# FlybackCape.net
KiCad netlist of a schematic drawn in EAGLE
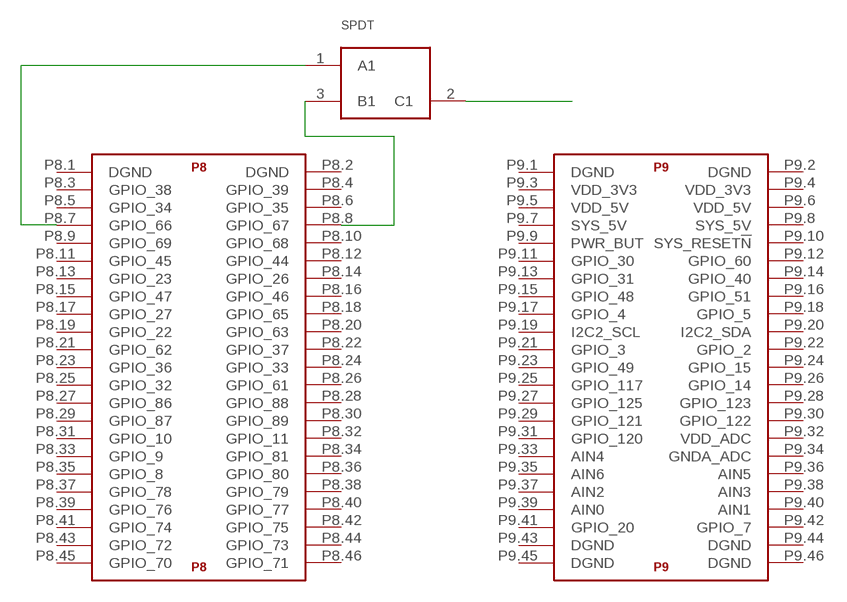
[diagram p0: schematic, sheet 1]
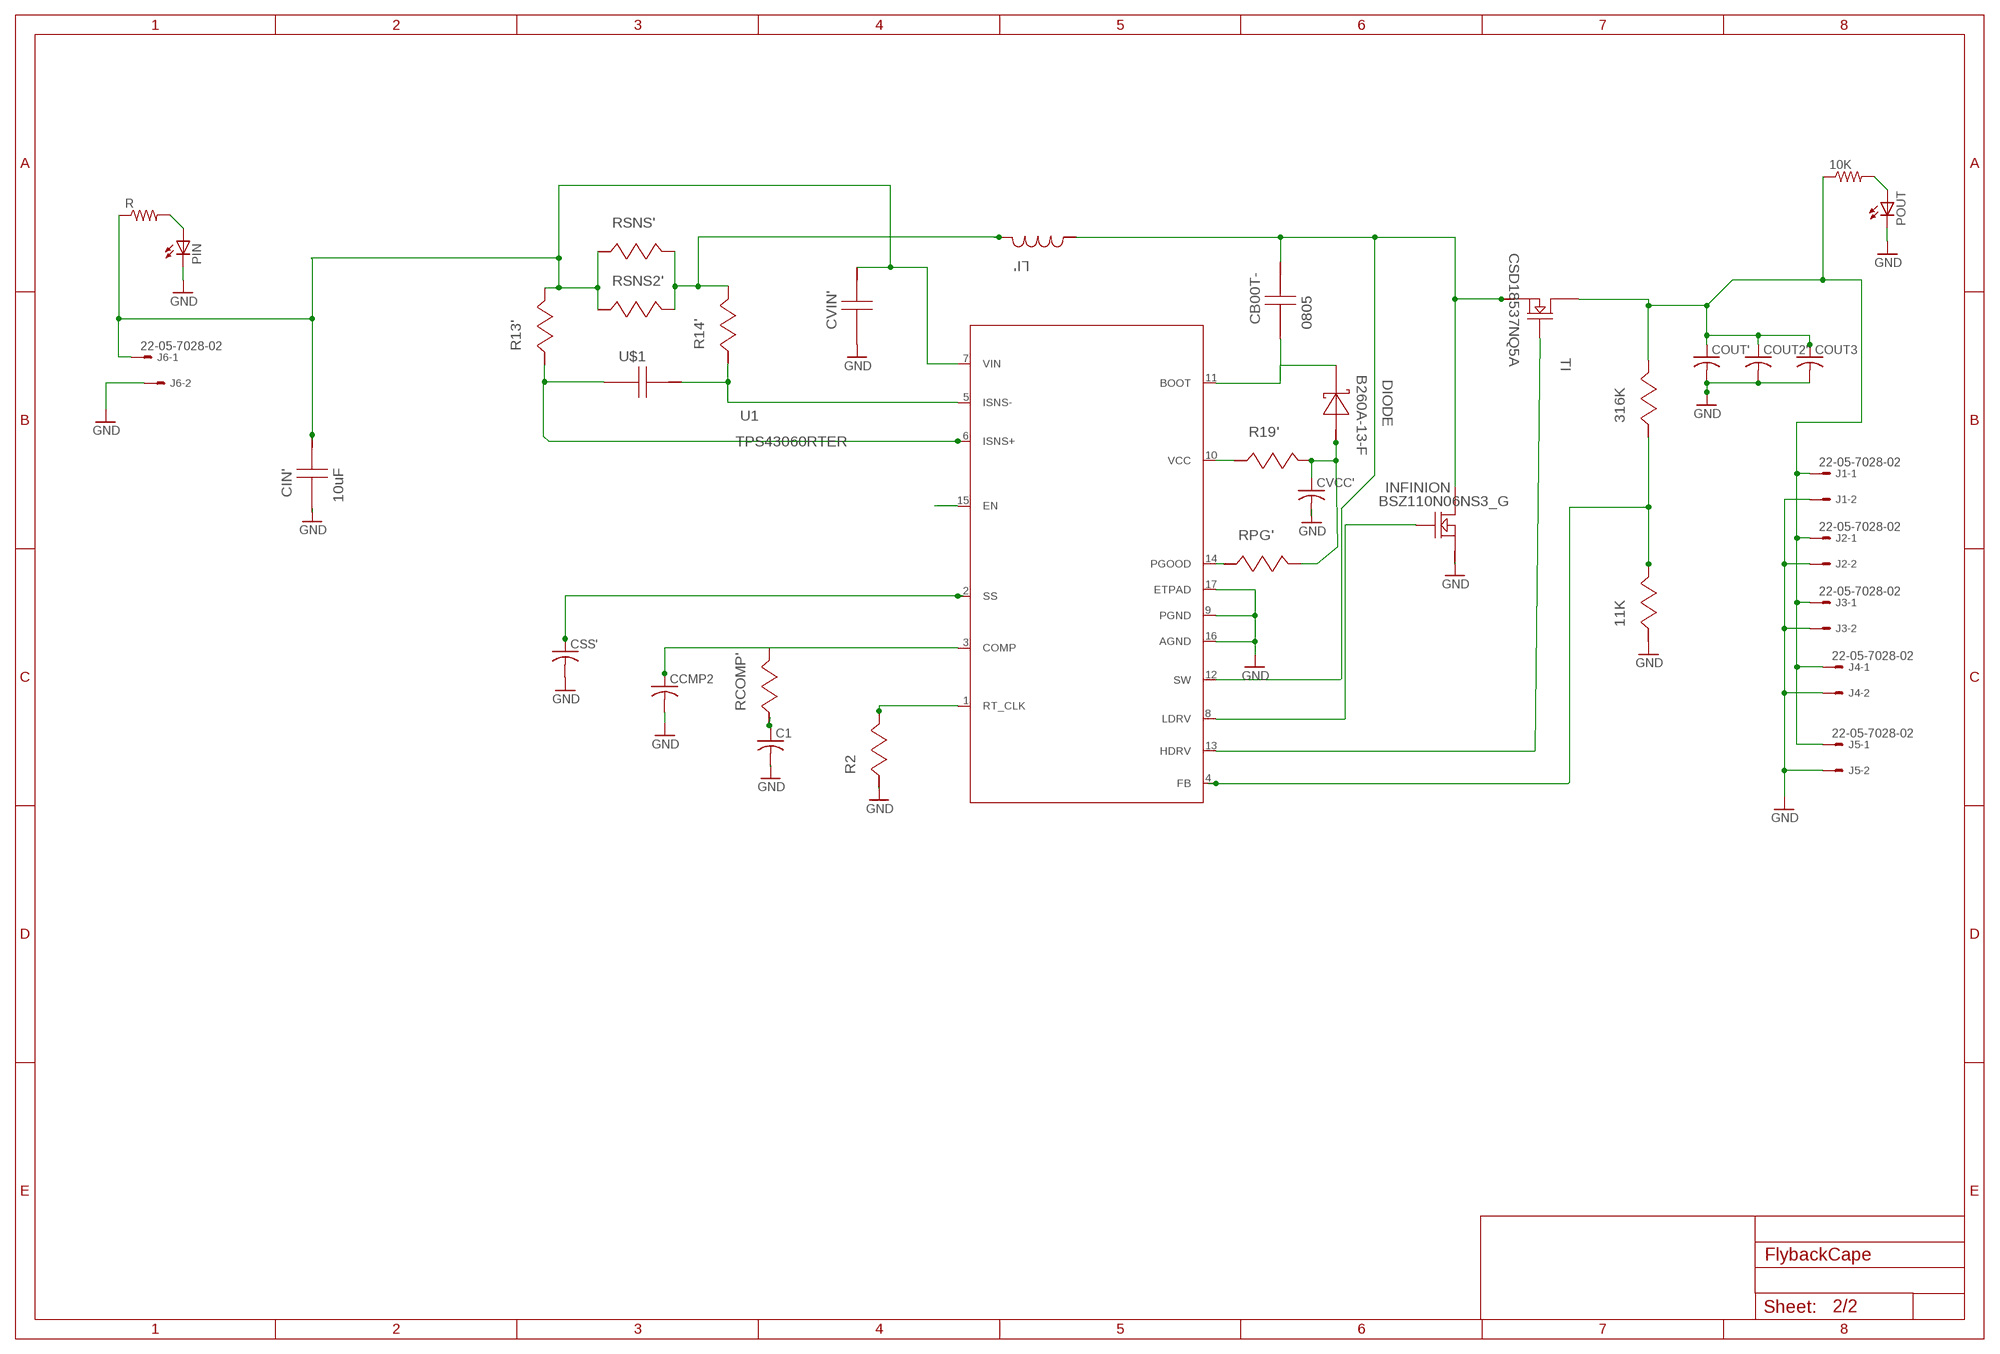
[diagram p1: schematic, sheet 2]

(export (version "E")
  (design (tool "Eeschema 10.0.6"))
  (components
    (comp (ref "10K")
      (value "R-US_R1206")
      (footprint "eagle-import:R1206")
      (libsource (lib "eagle-import") (part "R-US_R1206"))
    )
    (comp (ref "11K")
      (value "CRCW0402110KFKED")
      (footprint "eagle-import:0402")
      (fields (field (name "POWER") "0.063") (field (name "TOLERANCE") "1.0"))
      (libsource (lib "eagle-import") (part "CRCW0402110KFKED"))
    )
    (comp (ref "316K")
      (value "CRCW0402110KFKED")
      (footprint "eagle-import:0402")
      (fields (field (name "POWER") "0.063") (field (name "TOLERANCE") "1.0"))
      (libsource (lib "eagle-import") (part "CRCW0402110KFKED"))
    )
    (comp (ref "C1")
      (value "C-USC0805")
      (footprint "eagle-import:C0805")
      (libsource (lib "eagle-import") (part "C-USC0805"))
    )
    (comp (ref "CB00T-")
      (value "0805")
      (footprint "eagle-import:0805")
      (fields (field (name "MANUFACTURER_PART_NUMBER") "08053C104KAT2A"))
      (libsource (lib "eagle-import") (part "08053C104KAT2A"))
    )
    (comp (ref "CCMP2")
      (value "C-USC0402")
      (footprint "eagle-import:C0402")
      (libsource (lib "eagle-import") (part "C-USC0402"))
    )
    (comp (ref "CIN'")
      (value "10uF")
      (footprint "eagle-import:1210")
      (fields (field (name "MANUFACTURER_PART_NUMBER") "C3225X7S2A475M"))
      (libsource (lib "eagle-import") (part "C3225X7S2A475M"))
    )
    (comp (ref "COUT'")
      (value "C-USC1812")
      (footprint "eagle-import:C1812")
      (libsource (lib "eagle-import") (part "C-USC1812"))
    )
    (comp (ref "COUT2'")
      (value "C-USC1812")
      (footprint "eagle-import:C1812")
      (libsource (lib "eagle-import") (part "C-USC1812"))
    )
    (comp (ref "COUT3")
      (value "C-USC1812")
      (footprint "eagle-import:C1812")
      (libsource (lib "eagle-import") (part "C-USC1812"))
    )
    (comp (ref "CSS'")
      (value "C-USC0603K")
      (footprint "eagle-import:C0603K")
      (libsource (lib "eagle-import") (part "C-USC0603K"))
    )
    (comp (ref "CVCC'")
      (value "C-USC0805")
      (footprint "eagle-import:C0805")
      (libsource (lib "eagle-import") (part "C-USC0805"))
    )
    (comp (ref "CVIN'")
      (value "08053C104KAT2A")
      (footprint "eagle-import:0805")
      (libsource (lib "eagle-import") (part "08053C104KAT2A"))
    )
    (comp (ref "DIODE")
      (value "B260A-13-F")
      (footprint "eagle-import:SMA")
      (libsource (lib "eagle-import") (part "B260A-13-F"))
    )
    (comp (ref "INFINION")
      (value "BSZ110N06NS3_G")
      (footprint "eagle-import:PG-TSDSON-8")
      (fields (field (name "MANUFACTURER_PART_NUMBER") "BSZ110N06NS3 G"))
      (libsource (lib "eagle-import") (part "BSZ110N06NS3_G"))
    )
    (comp (ref "J1")
      (value "22-05-7028-02")
      (footprint "eagle-import:7395-02")
      (libsource (lib "eagle-import") (part "22-?-0205-7028"))
    )
    (comp (ref "J2")
      (value "22-05-7028-02")
      (footprint "eagle-import:7395-02")
      (libsource (lib "eagle-import") (part "22-?-0205-7028"))
    )
    (comp (ref "J3")
      (value "22-05-7028-02")
      (footprint "eagle-import:7395-02")
      (libsource (lib "eagle-import") (part "22-?-0205-7028"))
    )
    (comp (ref "J4")
      (value "22-05-7028-02")
      (footprint "eagle-import:7395-02")
      (libsource (lib "eagle-import") (part "22-?-0205-7028"))
    )
    (comp (ref "J5")
      (value "22-05-7028-02")
      (footprint "eagle-import:7395-02")
      (libsource (lib "eagle-import") (part "22-?-0205-7028"))
    )
    (comp (ref "J6")
      (value "22-05-7028-02")
      (footprint "eagle-import:7395-02")
      (libsource (lib "eagle-import") (part "22-?-0205-7028"))
    )
    (comp (ref "LI'")
      (value "MSS1210-153MEB")
      (footprint "eagle-import:MSS1210")
      (fields (field (name "MANUFACTURER") "CoilCraft"))
      (libsource (lib "eagle-import") (part "MSS1210-153MEB"))
    )
    (comp (ref "PIN")
      (value "LEDCHIPLED_1206")
      (footprint "eagle-import:CHIPLED_1206")
      (libsource (lib "eagle-import") (part "LEDCHIPLED_1206"))
    )
    (comp (ref "POUT")
      (value "LEDCHIPLED_1206")
      (footprint "eagle-import:CHIPLED_1206")
      (libsource (lib "eagle-import") (part "LEDCHIPLED_1206"))
    )
    (comp (ref "R")
      (value "R-US_R1206")
      (footprint "eagle-import:R1206")
      (libsource (lib "eagle-import") (part "R-US_R1206"))
    )
    (comp (ref "R2")
      (value "CRCW04023K32FKED")
      (footprint "eagle-import:0402")
      (fields (field (name "POWER") "0.063") (field (name "TOLERANCE") "1.0"))
      (libsource (lib "eagle-import") (part "CRCW04023K32FKED"))
    )
    (comp (ref "R13'")
      (value "CRCW04022R00FKED")
      (footprint "eagle-import:0402")
      (fields (field (name "POWER") "0.063") (field (name "TOLERANCE") "1.0"))
      (libsource (lib "eagle-import") (part "CRCW04022R00FKED"))
    )
    (comp (ref "R14'")
      (value "CRCW04022R00FKED")
      (footprint "eagle-import:0402")
      (fields (field (name "POWER") "0.063") (field (name "TOLERANCE") "1.0"))
      (libsource (lib "eagle-import") (part "CRCW04022R00FKED"))
    )
    (comp (ref "R19'")
      (value "CRCW04022R00FKED")
      (footprint "eagle-import:0402")
      (fields (field (name "POWER") "0.063") (field (name "TOLERANCE") "1.0"))
      (libsource (lib "eagle-import") (part "CRCW04022R00FKED"))
    )
    (comp (ref "RCOMP'")
      (value "CRCW04023K32FKED")
      (footprint "eagle-import:0402")
      (fields (field (name "POWER") "0.063") (field (name "TOLERANCE") "1.0"))
      (libsource (lib "eagle-import") (part "CRCW04023K32FKED"))
    )
    (comp (ref "RPG'")
      (value "CRCW0402100KFKED")
      (footprint "eagle-import:0402")
      (fields (field (name "POWER") "0.063") (field (name "TOLERANCE") "1.0"))
      (libsource (lib "eagle-import") (part "CRCW0402100KFKED"))
    )
    (comp (ref "RSNS'")
      (value "PRL1632-R012-F-T1")
      (footprint "eagle-import:1206")
      (fields (field (name "POWER") "1.0"))
      (libsource (lib "eagle-import") (part "PRL1632-R012-F-T1"))
    )
    (comp (ref "RSNS2'")
      (value "PRL1632-R012-F-T1")
      (footprint "eagle-import:1206")
      (fields (field (name "POWER") "1.0"))
      (libsource (lib "eagle-import") (part "PRL1632-R012-F-T1"))
    )
    (comp (ref "TI")
      (value "CSD18537NQ5A")
      (footprint "eagle-import:TRANS_NEXFET_Q5A")
      (libsource (lib "eagle-import") (part "CSD18537NQ5A"))
    )
    (comp (ref "U$1")
      (value "GRM188R61C106MA73D")
      (footprint "eagle-import:0603")
      (libsource (lib "eagle-import") (part "GRM188R61C106MA73D"))
    )
    (comp (ref "U1")
      (value "TPS43060RTER")
      (footprint "eagle-import:S-PVQFN-N16")
      (libsource (lib "eagle-import") (part "TPS43060RTER"))
    )
    (comp (ref "SPDT")
      (value "SPDT_SWITCH")
      (footprint "eagle-import:SPDT")
      (libsource (lib "eagle-import") (part "SPDT_SWITCH"))
    )
    (comp (ref "U$2")
      (value "BEAGLE_BONE_BLACK_CAPE")
      (footprint "eagle-import:BEAGLE_BONE_BLACK_CAPE")
      (libsource (lib "eagle-import") (part "BEAGLE_BONE_BLACK_CAPE"))
    )
  )
  (nets
    (net (code "1") (name "EN") (class "Default")
      (node (ref "SPDT") (pin "2") (pinfunction "C1_2") (pintype "bidirectional"))
      (node (ref "U1") (pin "15") (pinfunction "EN_15") (pintype "passive"))
    )
    (net (code "2") (name "GND") (class "Default")
      (node (ref "11K") (pin "2") (pinfunction "2_2") (pintype "passive"))
      (node (ref "C1") (pin "2") (pinfunction "2_2") (pintype "passive"))
      (node (ref "CCMP2") (pin "2") (pinfunction "2_2") (pintype "passive"))
      (node (ref "CIN'") (pin "2") (pinfunction "2_2") (pintype "passive"))
      (node (ref "COUT'") (pin "2") (pinfunction "2_2") (pintype "passive"))
      (node (ref "COUT2'") (pin "2") (pinfunction "2_2") (pintype "passive"))
      (node (ref "COUT3") (pin "2") (pinfunction "2_2") (pintype "passive"))
      (node (ref "CSS'") (pin "2") (pinfunction "2_2") (pintype "passive"))
      (node (ref "CVCC'") (pin "2") (pinfunction "2_2") (pintype "passive"))
      (node (ref "CVIN'") (pin "2") (pinfunction "2_2") (pintype "passive"))
      (node (ref "INFINION") (pin "1") (pinfunction "SOURCE_2_1") (pintype "passive"))
      (node (ref "INFINION") (pin "2") (pinfunction "SOURCE_2_2") (pintype "passive"))
      (node (ref "INFINION") (pin "3") (pinfunction "SOURCE_2_3") (pintype "passive"))
      (node (ref "J1") (pin "2") (pinfunction "S_2") (pintype "passive"))
      (node (ref "J2") (pin "2") (pinfunction "S_2") (pintype "passive"))
      (node (ref "J3") (pin "2") (pinfunction "S_2") (pintype "passive"))
      (node (ref "J4") (pin "2") (pinfunction "S_2") (pintype "passive"))
      (node (ref "J5") (pin "2") (pinfunction "S_2") (pintype "passive"))
      (node (ref "J6") (pin "2") (pinfunction "S_2") (pintype "passive"))
      (node (ref "PIN") (pin "C") (pinfunction "C_C") (pintype "passive"))
      (node (ref "POUT") (pin "C") (pinfunction "C_C") (pintype "passive"))
      (node (ref "R2") (pin "2") (pinfunction "2_2") (pintype "passive"))
      (node (ref "U1") (pin "16") (pinfunction "AGND_16") (pintype "passive"))
      (node (ref "U1") (pin "17") (pinfunction "ETPAD_17") (pintype "passive"))
      (node (ref "U1") (pin "9") (pinfunction "PGND_9") (pintype "passive"))
    )
    (net (code "3") (name "Net-(10K-Pad2)") (class "Default")
      (node (ref "10K") (pin "2") (pinfunction "2_2") (pintype "passive"))
      (node (ref "POUT") (pin "A") (pinfunction "A_A") (pintype "passive"))
    )
    (net (code "4") (name "Net-(C1-Pad1)") (class "Default")
      (node (ref "C1") (pin "1") (pinfunction "1_1") (pintype "passive"))
      (node (ref "RCOMP'") (pin "2") (pinfunction "2_2") (pintype "passive"))
    )
    (net (code "5") (name "Net-(DIODE-A)") (class "Default")
      (node (ref "CVCC'") (pin "1") (pinfunction "1_1") (pintype "passive"))
      (node (ref "DIODE") (pin "2") (pinfunction "A_2") (pintype "passive"))
      (node (ref "R19'") (pin "1") (pinfunction "1_1") (pintype "passive"))
      (node (ref "RPG'") (pin "1") (pinfunction "1_1") (pintype "passive"))
    )
    (net (code "6") (name "Net-(DIODE-K)") (class "Default")
      (node (ref "CB00T-") (pin "2") (pinfunction "2_2") (pintype "passive"))
      (node (ref "DIODE") (pin "1") (pinfunction "K_1") (pintype "passive"))
      (node (ref "U1") (pin "11") (pinfunction "BOOT_11") (pintype "passive"))
    )
    (net (code "7") (name "Net-(INFINION-GATE)") (class "Default")
      (node (ref "INFINION") (pin "4") (pinfunction "GATE_4") (pintype "passive"))
      (node (ref "U1") (pin "8") (pinfunction "LDRV_8") (pintype "passive"))
    )
    (net (code "8") (name "Net-(J1A-S)") (class "Default")
      (node (ref "10K") (pin "1") (pinfunction "1_1") (pintype "passive"))
      (node (ref "316K") (pin "1") (pinfunction "1_1") (pintype "passive"))
      (node (ref "COUT'") (pin "1") (pinfunction "1_1") (pintype "passive"))
      (node (ref "COUT2'") (pin "1") (pinfunction "1_1") (pintype "passive"))
      (node (ref "COUT3") (pin "1") (pinfunction "1_1") (pintype "passive"))
      (node (ref "J1") (pin "1") (pinfunction "S_1") (pintype "passive"))
      (node (ref "J2") (pin "1") (pinfunction "S_1") (pintype "passive"))
      (node (ref "J3") (pin "1") (pinfunction "S_1") (pintype "passive"))
      (node (ref "J4") (pin "1") (pinfunction "S_1") (pintype "passive"))
      (node (ref "J5") (pin "1") (pinfunction "S_1") (pintype "passive"))
      (node (ref "TI") (pin "5") (pinfunction "DRAIN_2_5") (pintype "passive"))
      (node (ref "TI") (pin "6") (pinfunction "DRAIN_2_6") (pintype "passive"))
      (node (ref "TI") (pin "7") (pinfunction "DRAIN_2_7") (pintype "passive"))
      (node (ref "TI") (pin "8") (pinfunction "DRAIN_2_8") (pintype "passive"))
      (node (ref "TI") (pin "9") (pinfunction "DRAIN_2_9") (pintype "passive"))
    )
    (net (code "9") (name "Net-(J6A-S)") (class "Default")
      (node (ref "CIN'") (pin "1") (pinfunction "1_1") (pintype "passive"))
      (node (ref "CVIN'") (pin "1") (pinfunction "1_1") (pintype "passive"))
      (node (ref "J6") (pin "1") (pinfunction "S_1") (pintype "passive"))
      (node (ref "R") (pin "1") (pinfunction "1_1") (pintype "passive"))
      (node (ref "R13'") (pin "1") (pinfunction "1_1") (pintype "passive"))
      (node (ref "RSNS'") (pin "2") (pinfunction "2_2") (pintype "passive"))
      (node (ref "RSNS2'") (pin "2") (pinfunction "2_2") (pintype "passive"))
      (node (ref "U1") (pin "7") (pinfunction "VIN_7") (pintype "passive"))
    )
    (net (code "10") (name "Net-(LI'-Pad1)") (class "Default")
      (node (ref "LI'") (pin "1") (pinfunction "1_1") (pintype "passive"))
      (node (ref "R14'") (pin "1") (pinfunction "1_1") (pintype "passive"))
      (node (ref "RSNS'") (pin "1") (pinfunction "1_1") (pintype "passive"))
      (node (ref "RSNS2'") (pin "1") (pinfunction "1_1") (pintype "passive"))
    )
    (net (code "11") (name "Net-(PIN-PadA)") (class "Default")
      (node (ref "PIN") (pin "A") (pinfunction "A_A") (pintype "passive"))
      (node (ref "R") (pin "2") (pinfunction "2_2") (pintype "passive"))
    )
    (net (code "12") (name "Net-(SPDT-A1)") (class "Default")
      (node (ref "SPDT") (pin "1") (pinfunction "A1_1") (pintype "bidirectional"))
      (node (ref "U$2") (pin "P8.7") (pinfunction "GPIO_66_P8.7") (pintype "bidirectional"))
    )
    (net (code "13") (name "Net-(SPDT-B1)") (class "Default")
      (node (ref "SPDT") (pin "3") (pinfunction "B1_3") (pintype "bidirectional"))
      (node (ref "U$2") (pin "P8.8") (pinfunction "GPIO_67_P8.8") (pintype "bidirectional"))
    )
    (net (code "14") (name "Net-(TI-GATE)") (class "Default")
      (node (ref "TI") (pin "4") (pinfunction "GATE_4") (pintype "passive"))
      (node (ref "U1") (pin "13") (pinfunction "HDRV_13") (pintype "passive"))
    )
    (net (code "15") (name "Net-(U1-COMP)") (class "Default")
      (node (ref "CCMP2") (pin "1") (pinfunction "1_1") (pintype "passive"))
      (node (ref "RCOMP'") (pin "1") (pinfunction "1_1") (pintype "passive"))
      (node (ref "U1") (pin "3") (pinfunction "COMP_3") (pintype "passive"))
    )
    (net (code "16") (name "Net-(U1-FB)") (class "Default")
      (node (ref "11K") (pin "1") (pinfunction "1_1") (pintype "passive"))
      (node (ref "316K") (pin "2") (pinfunction "2_2") (pintype "passive"))
      (node (ref "U1") (pin "4") (pinfunction "FB_4") (pintype "passive"))
    )
    (net (code "17") (name "Net-(U1-ISNS+)") (class "Default")
      (node (ref "R13'") (pin "2") (pinfunction "2_2") (pintype "passive"))
      (node (ref "U$1") (pin "2") (pinfunction "2_2") (pintype "passive"))
      (node (ref "U1") (pin "6") (pinfunction "ISNS+_6") (pintype "passive"))
    )
    (net (code "18") (name "Net-(U1-ISNS-)") (class "Default")
      (node (ref "R14'") (pin "2") (pinfunction "2_2") (pintype "passive"))
      (node (ref "U$1") (pin "1") (pinfunction "1_1") (pintype "passive"))
      (node (ref "U1") (pin "5") (pinfunction "ISNS-_5") (pintype "passive"))
    )
    (net (code "19") (name "Net-(U1-PGOOD)") (class "Default")
      (node (ref "RPG'") (pin "2") (pinfunction "2_2") (pintype "passive"))
      (node (ref "U1") (pin "14") (pinfunction "PGOOD_14") (pintype "passive"))
    )
    (net (code "20") (name "Net-(U1-RT_CLK)") (class "Default")
      (node (ref "R2") (pin "1") (pinfunction "1_1") (pintype "passive"))
      (node (ref "U1") (pin "1") (pinfunction "RT_CLK_1") (pintype "passive"))
    )
    (net (code "21") (name "Net-(U1-SS)") (class "Default")
      (node (ref "CSS'") (pin "1") (pinfunction "1_1") (pintype "passive"))
      (node (ref "U1") (pin "2") (pinfunction "SS_2") (pintype "passive"))
    )
    (net (code "22") (name "Net-(U1-SW)") (class "Default")
      (node (ref "CB00T-") (pin "1") (pinfunction "1_1") (pintype "passive"))
      (node (ref "INFINION") (pin "5") (pinfunction "DRAIN_2_5") (pintype "passive"))
      (node (ref "INFINION") (pin "6") (pinfunction "DRAIN_2_6") (pintype "passive"))
      (node (ref "INFINION") (pin "7") (pinfunction "DRAIN_2_7") (pintype "passive"))
      (node (ref "INFINION") (pin "8") (pinfunction "DRAIN_2_8") (pintype "passive"))
      (node (ref "INFINION") (pin "9") (pinfunction "DRAIN_2_9") (pintype "passive"))
      (node (ref "LI'") (pin "2") (pinfunction "2_2") (pintype "passive"))
      (node (ref "TI") (pin "1") (pinfunction "SOURCE_2_1") (pintype "passive"))
      (node (ref "TI") (pin "2") (pinfunction "SOURCE_2_2") (pintype "passive"))
      (node (ref "TI") (pin "3") (pinfunction "SOURCE_2_3") (pintype "passive"))
      (node (ref "U1") (pin "12") (pinfunction "SW_12") (pintype "passive"))
    )
    (net (code "23") (name "Net-(U1-VCC)") (class "Default")
      (node (ref "R19'") (pin "2") (pinfunction "2_2") (pintype "passive"))
      (node (ref "U1") (pin "10") (pinfunction "VCC_10") (pintype "passive"))
    )
    (net (code "24") (name "unconnected-(U$2A-DGND-PadP8.1)") (class "Default")
      (node (ref "U$2") (pin "P8.1") (pinfunction "DGND_P8.1") (pintype "bidirectional"))
    )
    (net (code "25") (name "unconnected-(U$2A-DGND-PadP8.2)") (class "Default")
      (node (ref "U$2") (pin "P8.2") (pinfunction "DGND_P8.2") (pintype "bidirectional"))
    )
    (net (code "26") (name "unconnected-(U$2A-GPIO_8-PadP8.35)") (class "Default")
      (node (ref "U$2") (pin "P8.35") (pinfunction "GPIO_8_P8.35") (pintype "bidirectional"))
    )
    (net (code "27") (name "unconnected-(U$2A-GPIO_9-PadP8.33)") (class "Default")
      (node (ref "U$2") (pin "P8.33") (pinfunction "GPIO_9_P8.33") (pintype "bidirectional"))
    )
    (net (code "28") (name "unconnected-(U$2A-GPIO_10-PadP8.31)") (class "Default")
      (node (ref "U$2") (pin "P8.31") (pinfunction "GPIO_10_P8.31") (pintype "bidirectional"))
    )
    (net (code "29") (name "unconnected-(U$2A-GPIO_11-PadP8.32)") (class "Default")
      (node (ref "U$2") (pin "P8.32") (pinfunction "GPIO_11_P8.32") (pintype "bidirectional"))
    )
    (net (code "30") (name "unconnected-(U$2A-GPIO_22-PadP8.19)") (class "Default")
      (node (ref "U$2") (pin "P8.19") (pinfunction "GPIO_22_P8.19") (pintype "bidirectional"))
    )
    (net (code "31") (name "unconnected-(U$2A-GPIO_23-PadP8.13)") (class "Default")
      (node (ref "U$2") (pin "P8.13") (pinfunction "GPIO_23_P8.13") (pintype "bidirectional"))
    )
    (net (code "32") (name "unconnected-(U$2A-GPIO_26-PadP8.14)") (class "Default")
      (node (ref "U$2") (pin "P8.14") (pinfunction "GPIO_26_P8.14") (pintype "bidirectional"))
    )
    (net (code "33") (name "unconnected-(U$2A-GPIO_27-PadP8.17)") (class "Default")
      (node (ref "U$2") (pin "P8.17") (pinfunction "GPIO_27_P8.17") (pintype "bidirectional"))
    )
    (net (code "34") (name "unconnected-(U$2A-GPIO_32-PadP8.25)") (class "Default")
      (node (ref "U$2") (pin "P8.25") (pinfunction "GPIO_32_P8.25") (pintype "bidirectional"))
    )
    (net (code "35") (name "unconnected-(U$2A-GPIO_33-PadP8.24)") (class "Default")
      (node (ref "U$2") (pin "P8.24") (pinfunction "GPIO_33_P8.24") (pintype "bidirectional"))
    )
    (net (code "36") (name "unconnected-(U$2A-GPIO_34-PadP8.5)") (class "Default")
      (node (ref "U$2") (pin "P8.5") (pinfunction "GPIO_34_P8.5") (pintype "bidirectional"))
    )
    (net (code "37") (name "unconnected-(U$2A-GPIO_35-PadP8.6)") (class "Default")
      (node (ref "U$2") (pin "P8.6") (pinfunction "GPIO_35_P8.6") (pintype "bidirectional"))
    )
    (net (code "38") (name "unconnected-(U$2A-GPIO_36-PadP8.23)") (class "Default")
      (node (ref "U$2") (pin "P8.23") (pinfunction "GPIO_36_P8.23") (pintype "bidirectional"))
    )
    (net (code "39") (name "unconnected-(U$2A-GPIO_37-PadP8.22)") (class "Default")
      (node (ref "U$2") (pin "P8.22") (pinfunction "GPIO_37_P8.22") (pintype "bidirectional"))
    )
    (net (code "40") (name "unconnected-(U$2A-GPIO_38-PadP8.3)") (class "Default")
      (node (ref "U$2") (pin "P8.3") (pinfunction "GPIO_38_P8.3") (pintype "bidirectional"))
    )
    (net (code "41") (name "unconnected-(U$2A-GPIO_39-PadP8.4)") (class "Default")
      (node (ref "U$2") (pin "P8.4") (pinfunction "GPIO_39_P8.4") (pintype "bidirectional"))
    )
    (net (code "42") (name "unconnected-(U$2A-GPIO_44-PadP8.12)") (class "Default")
      (node (ref "U$2") (pin "P8.12") (pinfunction "GPIO_44_P8.12") (pintype "bidirectional"))
    )
    (net (code "43") (name "unconnected-(U$2A-GPIO_45-PadP8.11)") (class "Default")
      (node (ref "U$2") (pin "P8.11") (pinfunction "GPIO_45_P8.11") (pintype "bidirectional"))
    )
    (net (code "44") (name "unconnected-(U$2A-GPIO_46-PadP8.16)") (class "Default")
      (node (ref "U$2") (pin "P8.16") (pinfunction "GPIO_46_P8.16") (pintype "bidirectional"))
    )
    (net (code "45") (name "unconnected-(U$2A-GPIO_47-PadP8.15)") (class "Default")
      (node (ref "U$2") (pin "P8.15") (pinfunction "GPIO_47_P8.15") (pintype "bidirectional"))
    )
    (net (code "46") (name "unconnected-(U$2A-GPIO_61-PadP8.26)") (class "Default")
      (node (ref "U$2") (pin "P8.26") (pinfunction "GPIO_61_P8.26") (pintype "bidirectional"))
    )
    (net (code "47") (name "unconnected-(U$2A-GPIO_62-PadP8.21)") (class "Default")
      (node (ref "U$2") (pin "P8.21") (pinfunction "GPIO_62_P8.21") (pintype "bidirectional"))
    )
    (net (code "48") (name "unconnected-(U$2A-GPIO_63-PadP8.20)") (class "Default")
      (node (ref "U$2") (pin "P8.20") (pinfunction "GPIO_63_P8.20") (pintype "bidirectional"))
    )
    (net (code "49") (name "unconnected-(U$2A-GPIO_65-PadP8.18)") (class "Default")
      (node (ref "U$2") (pin "P8.18") (pinfunction "GPIO_65_P8.18") (pintype "bidirectional"))
    )
    (net (code "50") (name "unconnected-(U$2A-GPIO_68-PadP8.10)") (class "Default")
      (node (ref "U$2") (pin "P8.10") (pinfunction "GPIO_68_P8.10") (pintype "bidirectional"))
    )
    (net (code "51") (name "unconnected-(U$2A-GPIO_69-PadP8.9)") (class "Default")
      (node (ref "U$2") (pin "P8.9") (pinfunction "GPIO_69_P8.9") (pintype "bidirectional"))
    )
    (net (code "52") (name "unconnected-(U$2A-GPIO_70-PadP8.45)") (class "Default")
      (node (ref "U$2") (pin "P8.45") (pinfunction "GPIO_70_P8.45") (pintype "bidirectional"))
    )
    (net (code "53") (name "unconnected-(U$2A-GPIO_71-PadP8.46)") (class "Default")
      (node (ref "U$2") (pin "P8.46") (pinfunction "GPIO_71_P8.46") (pintype "bidirectional"))
    )
    (net (code "54") (name "unconnected-(U$2A-GPIO_72-PadP8.43)") (class "Default")
      (node (ref "U$2") (pin "P8.43") (pinfunction "GPIO_72_P8.43") (pintype "bidirectional"))
    )
    (net (code "55") (name "unconnected-(U$2A-GPIO_73-PadP8.44)") (class "Default")
      (node (ref "U$2") (pin "P8.44") (pinfunction "GPIO_73_P8.44") (pintype "bidirectional"))
    )
    (net (code "56") (name "unconnected-(U$2A-GPIO_74-PadP8.41)") (class "Default")
      (node (ref "U$2") (pin "P8.41") (pinfunction "GPIO_74_P8.41") (pintype "bidirectional"))
    )
    (net (code "57") (name "unconnected-(U$2A-GPIO_75-PadP8.42)") (class "Default")
      (node (ref "U$2") (pin "P8.42") (pinfunction "GPIO_75_P8.42") (pintype "bidirectional"))
    )
    (net (code "58") (name "unconnected-(U$2A-GPIO_76-PadP8.39)") (class "Default")
      (node (ref "U$2") (pin "P8.39") (pinfunction "GPIO_76_P8.39") (pintype "bidirectional"))
    )
    (net (code "59") (name "unconnected-(U$2A-GPIO_77-PadP8.40)") (class "Default")
      (node (ref "U$2") (pin "P8.40") (pinfunction "GPIO_77_P8.40") (pintype "bidirectional"))
    )
    (net (code "60") (name "unconnected-(U$2A-GPIO_78-PadP8.37)") (class "Default")
      (node (ref "U$2") (pin "P8.37") (pinfunction "GPIO_78_P8.37") (pintype "bidirectional"))
    )
    (net (code "61") (name "unconnected-(U$2A-GPIO_79-PadP8.38)") (class "Default")
      (node (ref "U$2") (pin "P8.38") (pinfunction "GPIO_79_P8.38") (pintype "bidirectional"))
    )
    (net (code "62") (name "unconnected-(U$2A-GPIO_80-PadP8.36)") (class "Default")
      (node (ref "U$2") (pin "P8.36") (pinfunction "GPIO_80_P8.36") (pintype "bidirectional"))
    )
    (net (code "63") (name "unconnected-(U$2A-GPIO_81-PadP8.34)") (class "Default")
      (node (ref "U$2") (pin "P8.34") (pinfunction "GPIO_81_P8.34") (pintype "bidirectional"))
    )
    (net (code "64") (name "unconnected-(U$2A-GPIO_86-PadP8.27)") (class "Default")
      (node (ref "U$2") (pin "P8.27") (pinfunction "GPIO_86_P8.27") (pintype "bidirectional"))
    )
    (net (code "65") (name "unconnected-(U$2A-GPIO_87-PadP8.29)") (class "Default")
      (node (ref "U$2") (pin "P8.29") (pinfunction "GPIO_87_P8.29") (pintype "bidirectional"))
    )
    (net (code "66") (name "unconnected-(U$2A-GPIO_88-PadP8.28)") (class "Default")
      (node (ref "U$2") (pin "P8.28") (pinfunction "GPIO_88_P8.28") (pintype "bidirectional"))
    )
    (net (code "67") (name "unconnected-(U$2A-GPIO_89-PadP8.30)") (class "Default")
      (node (ref "U$2") (pin "P8.30") (pinfunction "GPIO_89_P8.30") (pintype "bidirectional"))
    )
    (net (code "68") (name "unconnected-(U$2B-AIN0-PadP9.39)") (class "Default")
      (node (ref "U$2") (pin "P9.39") (pinfunction "AIN0_P9.39") (pintype "bidirectional"))
    )
    (net (code "69") (name "unconnected-(U$2B-AIN1-PadP9.40)") (class "Default")
      (node (ref "U$2") (pin "P9.40") (pinfunction "AIN1_P9.40") (pintype "bidirectional"))
    )
    (net (code "70") (name "unconnected-(U$2B-AIN2-PadP9.37)") (class "Default")
      (node (ref "U$2") (pin "P9.37") (pinfunction "AIN2_P9.37") (pintype "bidirectional"))
    )
    (net (code "71") (name "unconnected-(U$2B-AIN3-PadP9.38)") (class "Default")
      (node (ref "U$2") (pin "P9.38") (pinfunction "AIN3_P9.38") (pintype "bidirectional"))
    )
    (net (code "72") (name "unconnected-(U$2B-AIN4-PadP9.33)") (class "Default")
      (node (ref "U$2") (pin "P9.33") (pinfunction "AIN4_P9.33") (pintype "bidirectional"))
    )
    (net (code "73") (name "unconnected-(U$2B-AIN5-PadP9.36)") (class "Default")
      (node (ref "U$2") (pin "P9.36") (pinfunction "AIN5_P9.36") (pintype "bidirectional"))
    )
    (net (code "74") (name "unconnected-(U$2B-AIN6-PadP9.35)") (class "Default")
      (node (ref "U$2") (pin "P9.35") (pinfunction "AIN6_P9.35") (pintype "bidirectional"))
    )
    (net (code "75") (name "unconnected-(U$2B-DGND-PadP9.1)") (class "Default")
      (node (ref "U$2") (pin "P9.1") (pinfunction "DGND_P9.1") (pintype "bidirectional"))
    )
    (net (code "76") (name "unconnected-(U$2B-DGND-PadP9.2)") (class "Default")
      (node (ref "U$2") (pin "P9.2") (pinfunction "DGND_P9.2") (pintype "bidirectional"))
    )
    (net (code "77") (name "unconnected-(U$2B-DGND-PadP9.43)") (class "Default")
      (node (ref "U$2") (pin "P9.43") (pinfunction "DGND_P9.43") (pintype "bidirectional"))
    )
    (net (code "78") (name "unconnected-(U$2B-DGND-PadP9.44)") (class "Default")
      (node (ref "U$2") (pin "P9.44") (pinfunction "DGND_P9.44") (pintype "bidirectional"))
    )
    (net (code "79") (name "unconnected-(U$2B-DGND-PadP9.45)") (class "Default")
      (node (ref "U$2") (pin "P9.45") (pinfunction "DGND_P9.45") (pintype "bidirectional"))
    )
    (net (code "80") (name "unconnected-(U$2B-DGND-PadP9.46)") (class "Default")
      (node (ref "U$2") (pin "P9.46") (pinfunction "DGND_P9.46") (pintype "bidirectional"))
    )
    (net (code "81") (name "unconnected-(U$2B-GNDA_ADC-PadP9.34)") (class "Default")
      (node (ref "U$2") (pin "P9.34") (pinfunction "GNDA_ADC_P9.34") (pintype "bidirectional"))
    )
    (net (code "82") (name "unconnected-(U$2B-GPIO_2-PadP9.22)") (class "Default")
      (node (ref "U$2") (pin "P9.22") (pinfunction "GPIO_2_P9.22") (pintype "bidirectional"))
    )
    (net (code "83") (name "unconnected-(U$2B-GPIO_3-PadP9.21)") (class "Default")
      (node (ref "U$2") (pin "P9.21") (pinfunction "GPIO_3_P9.21") (pintype "bidirectional"))
    )
    (net (code "84") (name "unconnected-(U$2B-GPIO_4-PadP9.17)") (class "Default")
      (node (ref "U$2") (pin "P9.17") (pinfunction "GPIO_4_P9.17") (pintype "bidirectional"))
    )
    (net (code "85") (name "unconnected-(U$2B-GPIO_5-PadP9.18)") (class "Default")
      (node (ref "U$2") (pin "P9.18") (pinfunction "GPIO_5_P9.18") (pintype "bidirectional"))
    )
    (net (code "86") (name "unconnected-(U$2B-GPIO_7-PadP9.42)") (class "Default")
      (node (ref "U$2") (pin "P9.42") (pinfunction "GPIO_7_P9.42") (pintype "bidirectional"))
    )
    (net (code "87") (name "unconnected-(U$2B-GPIO_14-PadP9.26)") (class "Default")
      (node (ref "U$2") (pin "P9.26") (pinfunction "GPIO_14_P9.26") (pintype "bidirectional"))
    )
    (net (code "88") (name "unconnected-(U$2B-GPIO_15-PadP9.24)") (class "Default")
      (node (ref "U$2") (pin "P9.24") (pinfunction "GPIO_15_P9.24") (pintype "bidirectional"))
    )
    (net (code "89") (name "unconnected-(U$2B-GPIO_20-PadP9.41)") (class "Default")
      (node (ref "U$2") (pin "P9.41") (pinfunction "GPIO_20_P9.41") (pintype "bidirectional"))
    )
    (net (code "90") (name "unconnected-(U$2B-GPIO_30-PadP9.11)") (class "Default")
      (node (ref "U$2") (pin "P9.11") (pinfunction "GPIO_30_P9.11") (pintype "bidirectional"))
    )
    (net (code "91") (name "unconnected-(U$2B-GPIO_31-PadP9.13)") (class "Default")
      (node (ref "U$2") (pin "P9.13") (pinfunction "GPIO_31_P9.13") (pintype "bidirectional"))
    )
    (net (code "92") (name "unconnected-(U$2B-GPIO_40-PadP9.14)") (class "Default")
      (node (ref "U$2") (pin "P9.14") (pinfunction "GPIO_40_P9.14") (pintype "bidirectional"))
    )
    (net (code "93") (name "unconnected-(U$2B-GPIO_48-PadP9.15)") (class "Default")
      (node (ref "U$2") (pin "P9.15") (pinfunction "GPIO_48_P9.15") (pintype "bidirectional"))
    )
    (net (code "94") (name "unconnected-(U$2B-GPIO_49-PadP9.23)") (class "Default")
      (node (ref "U$2") (pin "P9.23") (pinfunction "GPIO_49_P9.23") (pintype "bidirectional"))
    )
    (net (code "95") (name "unconnected-(U$2B-GPIO_51-PadP9.16)") (class "Default")
      (node (ref "U$2") (pin "P9.16") (pinfunction "GPIO_51_P9.16") (pintype "bidirectional"))
    )
    (net (code "96") (name "unconnected-(U$2B-GPIO_60-PadP9.12)") (class "Default")
      (node (ref "U$2") (pin "P9.12") (pinfunction "GPIO_60_P9.12") (pintype "bidirectional"))
    )
    (net (code "97") (name "unconnected-(U$2B-GPIO_117-PadP9.25)") (class "Default")
      (node (ref "U$2") (pin "P9.25") (pinfunction "GPIO_117_P9.25") (pintype "bidirectional"))
    )
    (net (code "98") (name "unconnected-(U$2B-GPIO_120-PadP9.31)") (class "Default")
      (node (ref "U$2") (pin "P9.31") (pinfunction "GPIO_120_P9.31") (pintype "bidirectional"))
    )
    (net (code "99") (name "unconnected-(U$2B-GPIO_121-PadP9.29)") (class "Default")
      (node (ref "U$2") (pin "P9.29") (pinfunction "GPIO_121_P9.29") (pintype "bidirectional"))
    )
    (net (code "100") (name "unconnected-(U$2B-GPIO_122-PadP9.30)") (class "Default")
      (node (ref "U$2") (pin "P9.30") (pinfunction "GPIO_122_P9.30") (pintype "bidirectional"))
    )
    (net (code "101") (name "unconnected-(U$2B-GPIO_123-PadP9.28)") (class "Default")
      (node (ref "U$2") (pin "P9.28") (pinfunction "GPIO_123_P9.28") (pintype "bidirectional"))
    )
    (net (code "102") (name "unconnected-(U$2B-GPIO_125-PadP9.27)") (class "Default")
      (node (ref "U$2") (pin "P9.27") (pinfunction "GPIO_125_P9.27") (pintype "bidirectional"))
    )
    (net (code "103") (name "unconnected-(U$2B-I2C2_SCL-PadP9.19)") (class "Default")
      (node (ref "U$2") (pin "P9.19") (pinfunction "I2C2_SCL_P9.19") (pintype "bidirectional"))
    )
    (net (code "104") (name "unconnected-(U$2B-I2C2_SDA-PadP9.20)") (class "Default")
      (node (ref "U$2") (pin "P9.20") (pinfunction "I2C2_SDA_P9.20") (pintype "bidirectional"))
    )
    (net (code "105") (name "unconnected-(U$2B-PWR_BUT-PadP9.9)") (class "Default")
      (node (ref "U$2") (pin "P9.9") (pinfunction "PWR_BUT_P9.9") (pintype "bidirectional"))
    )
    (net (code "106") (name "unconnected-(U$2B-SYS_5V-PadP9.7)") (class "Default")
      (node (ref "U$2") (pin "P9.7") (pinfunction "SYS_5V_P9.7") (pintype "bidirectional"))
    )
    (net (code "107") (name "unconnected-(U$2B-SYS_5V-PadP9.8)") (class "Default")
      (node (ref "U$2") (pin "P9.8") (pinfunction "SYS_5V_P9.8") (pintype "bidirectional"))
    )
    (net (code "108") (name "unconnected-(U$2B-SYS_RESET~{N}-PadP9.10)") (class "Default")
      (node (ref "U$2") (pin "P9.10") (pinfunction "SYS_RESET~{N}_P9.10") (pintype "bidirectional"))
    )
    (net (code "109") (name "unconnected-(U$2B-VDD_3V3-PadP9.3)") (class "Default")
      (node (ref "U$2") (pin "P9.3") (pinfunction "VDD_3V3_P9.3") (pintype "bidirectional"))
    )
    (net (code "110") (name "unconnected-(U$2B-VDD_3V3-PadP9.4)") (class "Default")
      (node (ref "U$2") (pin "P9.4") (pinfunction "VDD_3V3_P9.4") (pintype "bidirectional"))
    )
    (net (code "111") (name "unconnected-(U$2B-VDD_5V-PadP9.5)") (class "Default")
      (node (ref "U$2") (pin "P9.5") (pinfunction "VDD_5V_P9.5") (pintype "bidirectional"))
    )
    (net (code "112") (name "unconnected-(U$2B-VDD_5V-PadP9.6)") (class "Default")
      (node (ref "U$2") (pin "P9.6") (pinfunction "VDD_5V_P9.6") (pintype "bidirectional"))
    )
    (net (code "113") (name "unconnected-(U$2B-VDD_ADC-PadP9.32)") (class "Default")
      (node (ref "U$2") (pin "P9.32") (pinfunction "VDD_ADC_P9.32") (pintype "bidirectional"))
    )
  )
)
